# FrontPanel.net
KiCad netlist of a schematic drawn in EAGLE
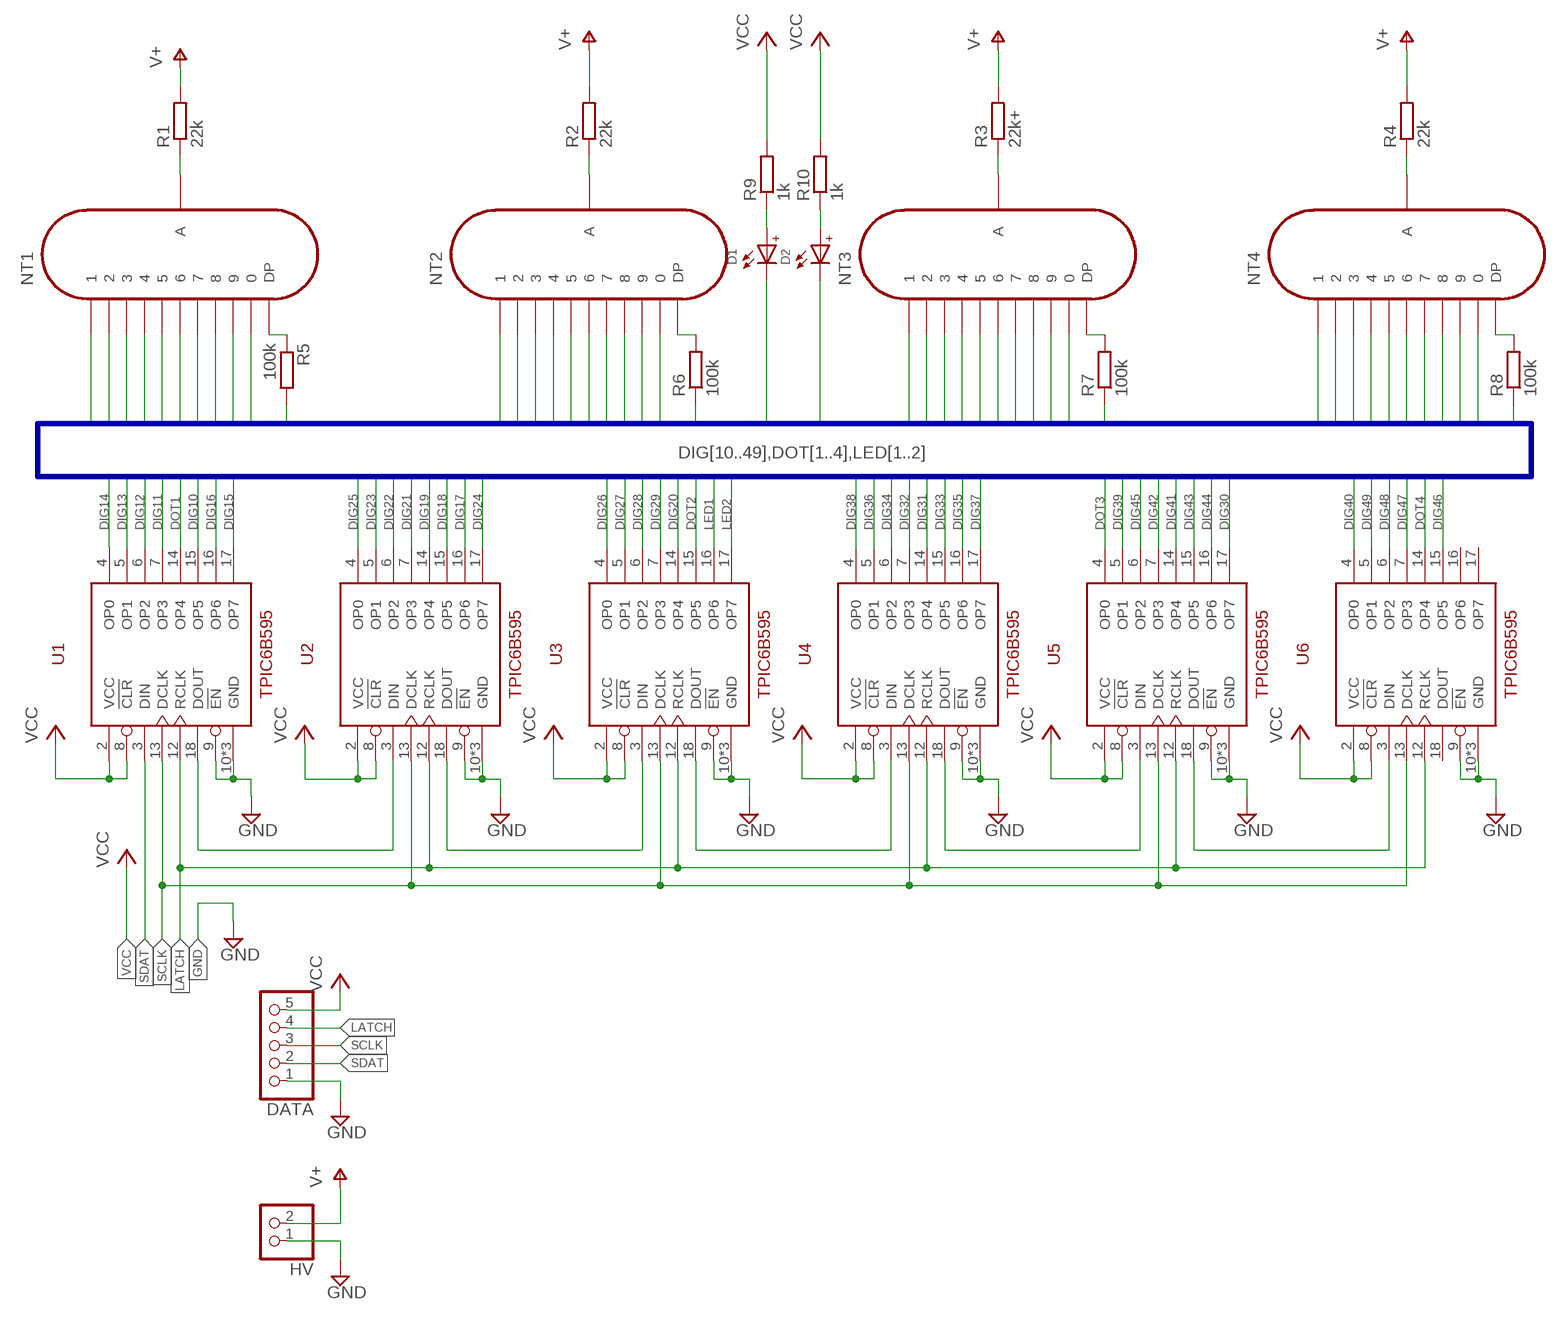
[diagram p0: schematic, sheet 1]

(export (version "E")
  (design (tool "Eeschema 10.0.6"))
  (components
    (comp (ref "D1")
      (value "RED/AMBER")
      (footprint "eagle-import:WL-SITW_154141XXBA210")
      (libsource (lib "eagle-import") (part "WL-SITW_3528_15414185BA210"))
    )
    (comp (ref "D2")
      (value "RED/AMBER")
      (footprint "eagle-import:WL-SITW_154141XXBA210")
      (libsource (lib "eagle-import") (part "WL-SITW_3528_15414185BA210"))
    )
    (comp (ref "DATA")
      (value ".1\" Header")
      (footprint "eagle-import:1X05")
      (libsource (lib "eagle-import") (part "PINHD-1X5"))
    )
    (comp (ref "HV")
      (value ".1\" Header")
      (footprint "eagle-import:1X02")
      (libsource (lib "eagle-import") (part "PINHD-1X2"))
    )
    (comp (ref "NT1")
      (value "IN-12B")
      (footprint "eagle-import:IN-12")
      (libsource (lib "eagle-import") (part "IN-12B"))
    )
    (comp (ref "NT2")
      (value "IN-12B")
      (footprint "eagle-import:IN-12")
      (libsource (lib "eagle-import") (part "IN-12B"))
    )
    (comp (ref "NT3")
      (value "IN-12B")
      (footprint "eagle-import:IN-12")
      (libsource (lib "eagle-import") (part "IN-12B"))
    )
    (comp (ref "NT4")
      (value "IN-12B")
      (footprint "eagle-import:IN-12")
      (libsource (lib "eagle-import") (part "IN-12B"))
    )
    (comp (ref "R1")
      (value "22k")
      (footprint "eagle-import:0207_10")
      (libsource (lib "eagle-import") (part "R-EU_0207/10"))
    )
    (comp (ref "R2")
      (value "22k")
      (footprint "eagle-import:0207_10")
      (libsource (lib "eagle-import") (part "R-EU_0207/10"))
    )
    (comp (ref "R3")
      (value "22k+")
      (footprint "eagle-import:0207_10")
      (libsource (lib "eagle-import") (part "R-EU_0207/10"))
    )
    (comp (ref "R4")
      (value "22k")
      (footprint "eagle-import:0207_10")
      (libsource (lib "eagle-import") (part "R-EU_0207/10"))
    )
    (comp (ref "R5")
      (value "100k")
      (footprint "eagle-import:0207_10")
      (libsource (lib "eagle-import") (part "R-EU_0207/10"))
    )
    (comp (ref "R6")
      (value "100k")
      (footprint "eagle-import:0207_10")
      (libsource (lib "eagle-import") (part "R-EU_0207/10"))
    )
    (comp (ref "R7")
      (value "100k")
      (footprint "eagle-import:0207_10")
      (libsource (lib "eagle-import") (part "R-EU_0207/10"))
    )
    (comp (ref "R8")
      (value "100k")
      (footprint "eagle-import:0207_10")
      (libsource (lib "eagle-import") (part "R-EU_0207/10"))
    )
    (comp (ref "R9")
      (value "1k")
      (footprint "eagle-import:0207_10")
      (libsource (lib "eagle-import") (part "R-EU_0207/10"))
    )
    (comp (ref "R10")
      (value "1k")
      (footprint "eagle-import:0207_10")
      (libsource (lib "eagle-import") (part "R-EU_0207/10"))
    )
    (comp (ref "U1")
      (value "TPIC6B595N")
      (footprint "eagle-import:PDIP-20")
      (libsource (lib "eagle-import") (part "TPIC6B595N"))
    )
    (comp (ref "U2")
      (value "TPIC6B595N")
      (footprint "eagle-import:PDIP-20")
      (libsource (lib "eagle-import") (part "TPIC6B595N"))
    )
    (comp (ref "U3")
      (value "TPIC6B595N")
      (footprint "eagle-import:PDIP-20")
      (libsource (lib "eagle-import") (part "TPIC6B595N"))
    )
    (comp (ref "U4")
      (value "TPIC6B595N")
      (footprint "eagle-import:PDIP-20")
      (libsource (lib "eagle-import") (part "TPIC6B595N"))
    )
    (comp (ref "U5")
      (value "TPIC6B595N")
      (footprint "eagle-import:PDIP-20")
      (libsource (lib "eagle-import") (part "TPIC6B595N"))
    )
    (comp (ref "U6")
      (value "TPIC6B595N")
      (footprint "eagle-import:PDIP-20")
      (libsource (lib "eagle-import") (part "TPIC6B595N"))
    )
  )
  (nets
    (net (code "1") (name "/DIG10") (class "Default")
      (node (ref "NT1") (pin "0") (pinfunction "0_0") (pintype "bidirectional"))
      (node (ref "U1") (pin "15") (pinfunction "OP5_15") (pintype "open_collector"))
    )
    (net (code "2") (name "/DIG11") (class "Default")
      (node (ref "NT1") (pin "1") (pinfunction "1_1") (pintype "bidirectional"))
      (node (ref "U1") (pin "7") (pinfunction "OP3_7") (pintype "open_collector"))
    )
    (net (code "3") (name "/DIG12") (class "Default")
      (node (ref "NT1") (pin "2") (pinfunction "2_2") (pintype "bidirectional"))
      (node (ref "U1") (pin "6") (pinfunction "OP2_6") (pintype "open_collector"))
    )
    (net (code "4") (name "/DIG13") (class "Default")
      (node (ref "NT1") (pin "3") (pinfunction "3_3") (pintype "bidirectional"))
      (node (ref "U1") (pin "5") (pinfunction "OP1_5") (pintype "open_collector"))
    )
    (net (code "5") (name "/DIG14") (class "Default")
      (node (ref "NT1") (pin "4") (pinfunction "4_4") (pintype "bidirectional"))
      (node (ref "U1") (pin "4") (pinfunction "OP0_4") (pintype "open_collector"))
    )
    (net (code "6") (name "/DIG15") (class "Default")
      (node (ref "NT1") (pin "5") (pinfunction "5_5") (pintype "bidirectional"))
      (node (ref "U1") (pin "17") (pinfunction "OP7_17") (pintype "open_collector"))
    )
    (net (code "7") (name "/DIG16") (class "Default")
      (node (ref "NT1") (pin "6") (pinfunction "6_6") (pintype "bidirectional"))
      (node (ref "U1") (pin "16") (pinfunction "OP6_16") (pintype "open_collector"))
    )
    (net (code "8") (name "/DIG17") (class "Default")
      (node (ref "NT1") (pin "7") (pinfunction "7_7") (pintype "bidirectional"))
      (node (ref "U2") (pin "16") (pinfunction "OP6_16") (pintype "open_collector"))
    )
    (net (code "9") (name "/DIG18") (class "Default")
      (node (ref "NT1") (pin "8") (pinfunction "8_8") (pintype "bidirectional"))
      (node (ref "U2") (pin "15") (pinfunction "OP5_15") (pintype "open_collector"))
    )
    (net (code "10") (name "/DIG19") (class "Default")
      (node (ref "NT1") (pin "9") (pinfunction "9_9") (pintype "bidirectional"))
      (node (ref "U2") (pin "14") (pinfunction "OP4_14") (pintype "open_collector"))
    )
    (net (code "11") (name "/DIG20") (class "Default")
      (node (ref "NT2") (pin "0") (pinfunction "0_0") (pintype "bidirectional"))
      (node (ref "U3") (pin "14") (pinfunction "OP4_14") (pintype "open_collector"))
    )
    (net (code "12") (name "/DIG21") (class "Default")
      (node (ref "NT2") (pin "1") (pinfunction "1_1") (pintype "bidirectional"))
      (node (ref "U2") (pin "7") (pinfunction "OP3_7") (pintype "open_collector"))
    )
    (net (code "13") (name "/DIG22") (class "Default")
      (node (ref "NT2") (pin "2") (pinfunction "2_2") (pintype "bidirectional"))
      (node (ref "U2") (pin "6") (pinfunction "OP2_6") (pintype "open_collector"))
    )
    (net (code "14") (name "/DIG23") (class "Default")
      (node (ref "NT2") (pin "3") (pinfunction "3_3") (pintype "bidirectional"))
      (node (ref "U2") (pin "5") (pinfunction "OP1_5") (pintype "open_collector"))
    )
    (net (code "15") (name "/DIG24") (class "Default")
      (node (ref "NT2") (pin "4") (pinfunction "4_4") (pintype "bidirectional"))
      (node (ref "U2") (pin "17") (pinfunction "OP7_17") (pintype "open_collector"))
    )
    (net (code "16") (name "/DIG25") (class "Default")
      (node (ref "NT2") (pin "5") (pinfunction "5_5") (pintype "bidirectional"))
      (node (ref "U2") (pin "4") (pinfunction "OP0_4") (pintype "open_collector"))
    )
    (net (code "17") (name "/DIG26") (class "Default")
      (node (ref "NT2") (pin "6") (pinfunction "6_6") (pintype "bidirectional"))
      (node (ref "U3") (pin "4") (pinfunction "OP0_4") (pintype "open_collector"))
    )
    (net (code "18") (name "/DIG27") (class "Default")
      (node (ref "NT2") (pin "7") (pinfunction "7_7") (pintype "bidirectional"))
      (node (ref "U3") (pin "5") (pinfunction "OP1_5") (pintype "open_collector"))
    )
    (net (code "19") (name "/DIG28") (class "Default")
      (node (ref "NT2") (pin "8") (pinfunction "8_8") (pintype "bidirectional"))
      (node (ref "U3") (pin "6") (pinfunction "OP2_6") (pintype "open_collector"))
    )
    (net (code "20") (name "/DIG29") (class "Default")
      (node (ref "NT2") (pin "9") (pinfunction "9_9") (pintype "bidirectional"))
      (node (ref "U3") (pin "7") (pinfunction "OP3_7") (pintype "open_collector"))
    )
    (net (code "21") (name "/DIG30") (class "Default")
      (node (ref "NT3") (pin "0") (pinfunction "0_0") (pintype "bidirectional"))
      (node (ref "U5") (pin "17") (pinfunction "OP7_17") (pintype "open_collector"))
    )
    (net (code "22") (name "/DIG31") (class "Default")
      (node (ref "NT3") (pin "1") (pinfunction "1_1") (pintype "bidirectional"))
      (node (ref "U4") (pin "14") (pinfunction "OP4_14") (pintype "open_collector"))
    )
    (net (code "23") (name "/DIG32") (class "Default")
      (node (ref "NT3") (pin "2") (pinfunction "2_2") (pintype "bidirectional"))
      (node (ref "U4") (pin "7") (pinfunction "OP3_7") (pintype "open_collector"))
    )
    (net (code "24") (name "/DIG33") (class "Default")
      (node (ref "NT3") (pin "3") (pinfunction "3_3") (pintype "bidirectional"))
      (node (ref "U4") (pin "15") (pinfunction "OP5_15") (pintype "open_collector"))
    )
    (net (code "25") (name "/DIG34") (class "Default")
      (node (ref "NT3") (pin "4") (pinfunction "4_4") (pintype "bidirectional"))
      (node (ref "U4") (pin "6") (pinfunction "OP2_6") (pintype "open_collector"))
    )
    (net (code "26") (name "/DIG35") (class "Default")
      (node (ref "NT3") (pin "5") (pinfunction "5_5") (pintype "bidirectional"))
      (node (ref "U4") (pin "16") (pinfunction "OP6_16") (pintype "open_collector"))
    )
    (net (code "27") (name "/DIG36") (class "Default")
      (node (ref "NT3") (pin "6") (pinfunction "6_6") (pintype "bidirectional"))
      (node (ref "U4") (pin "5") (pinfunction "OP1_5") (pintype "open_collector"))
    )
    (net (code "28") (name "/DIG37") (class "Default")
      (node (ref "NT3") (pin "7") (pinfunction "7_7") (pintype "bidirectional"))
      (node (ref "U4") (pin "17") (pinfunction "OP7_17") (pintype "open_collector"))
    )
    (net (code "29") (name "/DIG38") (class "Default")
      (node (ref "NT3") (pin "8") (pinfunction "8_8") (pintype "bidirectional"))
      (node (ref "U4") (pin "4") (pinfunction "OP0_4") (pintype "open_collector"))
    )
    (net (code "30") (name "/DIG39") (class "Default")
      (node (ref "NT3") (pin "9") (pinfunction "9_9") (pintype "bidirectional"))
      (node (ref "U5") (pin "5") (pinfunction "OP1_5") (pintype "open_collector"))
    )
    (net (code "31") (name "/DIG40") (class "Default")
      (node (ref "NT4") (pin "0") (pinfunction "0_0") (pintype "bidirectional"))
      (node (ref "U6") (pin "4") (pinfunction "OP0_4") (pintype "open_collector"))
    )
    (net (code "32") (name "/DIG41") (class "Default")
      (node (ref "NT4") (pin "1") (pinfunction "1_1") (pintype "bidirectional"))
      (node (ref "U5") (pin "14") (pinfunction "OP4_14") (pintype "open_collector"))
    )
    (net (code "33") (name "/DIG42") (class "Default")
      (node (ref "NT4") (pin "2") (pinfunction "2_2") (pintype "bidirectional"))
      (node (ref "U5") (pin "7") (pinfunction "OP3_7") (pintype "open_collector"))
    )
    (net (code "34") (name "/DIG43") (class "Default")
      (node (ref "NT4") (pin "3") (pinfunction "3_3") (pintype "bidirectional"))
      (node (ref "U5") (pin "15") (pinfunction "OP5_15") (pintype "open_collector"))
    )
    (net (code "35") (name "/DIG44") (class "Default")
      (node (ref "NT4") (pin "4") (pinfunction "4_4") (pintype "bidirectional"))
      (node (ref "U5") (pin "16") (pinfunction "OP6_16") (pintype "open_collector"))
    )
    (net (code "36") (name "/DIG45") (class "Default")
      (node (ref "NT4") (pin "5") (pinfunction "5_5") (pintype "bidirectional"))
      (node (ref "U5") (pin "6") (pinfunction "OP2_6") (pintype "open_collector"))
    )
    (net (code "37") (name "/DIG46") (class "Default")
      (node (ref "NT4") (pin "6") (pinfunction "6_6") (pintype "bidirectional"))
      (node (ref "U6") (pin "15") (pinfunction "OP5_15") (pintype "open_collector"))
    )
    (net (code "38") (name "/DIG47") (class "Default")
      (node (ref "NT4") (pin "7") (pinfunction "7_7") (pintype "bidirectional"))
      (node (ref "U6") (pin "7") (pinfunction "OP3_7") (pintype "open_collector"))
    )
    (net (code "39") (name "/DIG48") (class "Default")
      (node (ref "NT4") (pin "8") (pinfunction "8_8") (pintype "bidirectional"))
      (node (ref "U6") (pin "6") (pinfunction "OP2_6") (pintype "open_collector"))
    )
    (net (code "40") (name "/DIG49") (class "Default")
      (node (ref "NT4") (pin "9") (pinfunction "9_9") (pintype "bidirectional"))
      (node (ref "U6") (pin "5") (pinfunction "OP1_5") (pintype "open_collector"))
    )
    (net (code "41") (name "/DOT1") (class "Default")
      (node (ref "R5") (pin "2") (pinfunction "2_2") (pintype "passive"))
      (node (ref "U1") (pin "14") (pinfunction "OP4_14") (pintype "open_collector"))
    )
    (net (code "42") (name "/DOT2") (class "Default")
      (node (ref "R6") (pin "1") (pinfunction "1_1") (pintype "passive"))
      (node (ref "U3") (pin "15") (pinfunction "OP5_15") (pintype "open_collector"))
    )
    (net (code "43") (name "/DOT3") (class "Default")
      (node (ref "R7") (pin "1") (pinfunction "1_1") (pintype "passive"))
      (node (ref "U5") (pin "4") (pinfunction "OP0_4") (pintype "open_collector"))
    )
    (net (code "44") (name "/DOT4") (class "Default")
      (node (ref "R8") (pin "1") (pinfunction "1_1") (pintype "passive"))
      (node (ref "U6") (pin "14") (pinfunction "OP4_14") (pintype "open_collector"))
    )
    (net (code "45") (name "/LED1") (class "Default")
      (node (ref "D1") (pin "2") (pinfunction "-_2") (pintype "passive"))
      (node (ref "U3") (pin "16") (pinfunction "OP6_16") (pintype "open_collector"))
    )
    (net (code "46") (name "/LED2") (class "Default")
      (node (ref "D2") (pin "2") (pinfunction "-_2") (pintype "passive"))
      (node (ref "U3") (pin "17") (pinfunction "OP7_17") (pintype "open_collector"))
    )
    (net (code "48") (name "GND") (class "Default")
      (node (ref "DATA") (pin "1") (pinfunction "1_1") (pintype "passive"))
      (node (ref "HV") (pin "1") (pinfunction "1_1") (pintype "passive"))
      (node (ref "U1") (pin "10") (pinfunction "GND_10") (pintype "power_in"))
      (node (ref "U1") (pin "11") (pinfunction "GND_11") (pintype "power_in"))
      (node (ref "U1") (pin "19") (pinfunction "GND_19") (pintype "power_in"))
      (node (ref "U1") (pin "9") (pinfunction "~{EN}_9") (pintype "input"))
      (node (ref "U2") (pin "10") (pinfunction "GND_10") (pintype "power_in"))
      (node (ref "U2") (pin "11") (pinfunction "GND_11") (pintype "power_in"))
      (node (ref "U2") (pin "19") (pinfunction "GND_19") (pintype "power_in"))
      (node (ref "U2") (pin "9") (pinfunction "~{EN}_9") (pintype "input"))
      (node (ref "U3") (pin "10") (pinfunction "GND_10") (pintype "power_in"))
      (node (ref "U3") (pin "11") (pinfunction "GND_11") (pintype "power_in"))
      (node (ref "U3") (pin "19") (pinfunction "GND_19") (pintype "power_in"))
      (node (ref "U3") (pin "9") (pinfunction "~{EN}_9") (pintype "input"))
      (node (ref "U4") (pin "10") (pinfunction "GND_10") (pintype "power_in"))
      (node (ref "U4") (pin "11") (pinfunction "GND_11") (pintype "power_in"))
      (node (ref "U4") (pin "19") (pinfunction "GND_19") (pintype "power_in"))
      (node (ref "U4") (pin "9") (pinfunction "~{EN}_9") (pintype "input"))
      (node (ref "U5") (pin "10") (pinfunction "GND_10") (pintype "power_in"))
      (node (ref "U5") (pin "11") (pinfunction "GND_11") (pintype "power_in"))
      (node (ref "U5") (pin "19") (pinfunction "GND_19") (pintype "power_in"))
      (node (ref "U5") (pin "9") (pinfunction "~{EN}_9") (pintype "input"))
      (node (ref "U6") (pin "10") (pinfunction "GND_10") (pintype "power_in"))
      (node (ref "U6") (pin "11") (pinfunction "GND_11") (pintype "power_in"))
      (node (ref "U6") (pin "19") (pinfunction "GND_19") (pintype "power_in"))
      (node (ref "U6") (pin "9") (pinfunction "~{EN}_9") (pintype "input"))
    )
    (net (code "49") (name "LATCH") (class "Default")
      (node (ref "DATA") (pin "4") (pinfunction "4_4") (pintype "passive"))
      (node (ref "U1") (pin "12") (pinfunction "RCLK_12") (pintype "input"))
      (node (ref "U2") (pin "12") (pinfunction "RCLK_12") (pintype "input"))
      (node (ref "U3") (pin "12") (pinfunction "RCLK_12") (pintype "input"))
      (node (ref "U4") (pin "12") (pinfunction "RCLK_12") (pintype "input"))
      (node (ref "U5") (pin "12") (pinfunction "RCLK_12") (pintype "input"))
      (node (ref "U6") (pin "12") (pinfunction "RCLK_12") (pintype "input"))
    )
    (net (code "50") (name "Net-(D1-+)") (class "Default")
      (node (ref "D1") (pin "1") (pinfunction "+_1") (pintype "passive"))
      (node (ref "R9") (pin "1") (pinfunction "1_1") (pintype "passive"))
    )
    (net (code "51") (name "Net-(D2-+)") (class "Default")
      (node (ref "D2") (pin "1") (pinfunction "+_1") (pintype "passive"))
      (node (ref "R10") (pin "1") (pinfunction "1_1") (pintype "passive"))
    )
    (net (code "52") (name "Net-(NT1-DP)") (class "Default")
      (node (ref "NT1") (pin "LHDP") (pinfunction "DP_LHDP") (pintype "bidirectional"))
      (node (ref "R5") (pin "1") (pinfunction "1_1") (pintype "passive"))
    )
    (net (code "53") (name "Net-(NT1-PadA)") (class "Default")
      (node (ref "NT1") (pin "A") (pinfunction "A_A") (pintype "bidirectional"))
      (node (ref "R1") (pin "1") (pinfunction "1_1") (pintype "passive"))
    )
    (net (code "54") (name "Net-(NT2-DP)") (class "Default")
      (node (ref "NT2") (pin "LHDP") (pinfunction "DP_LHDP") (pintype "bidirectional"))
      (node (ref "R6") (pin "2") (pinfunction "2_2") (pintype "passive"))
    )
    (net (code "55") (name "Net-(NT2-PadA)") (class "Default")
      (node (ref "NT2") (pin "A") (pinfunction "A_A") (pintype "bidirectional"))
      (node (ref "R2") (pin "1") (pinfunction "1_1") (pintype "passive"))
    )
    (net (code "56") (name "Net-(NT3-DP)") (class "Default")
      (node (ref "NT3") (pin "LHDP") (pinfunction "DP_LHDP") (pintype "bidirectional"))
      (node (ref "R7") (pin "2") (pinfunction "2_2") (pintype "passive"))
    )
    (net (code "57") (name "Net-(NT3-PadA)") (class "Default")
      (node (ref "NT3") (pin "A") (pinfunction "A_A") (pintype "bidirectional"))
      (node (ref "R3") (pin "1") (pinfunction "1_1") (pintype "passive"))
    )
    (net (code "58") (name "Net-(NT4-DP)") (class "Default")
      (node (ref "NT4") (pin "LHDP") (pinfunction "DP_LHDP") (pintype "bidirectional"))
      (node (ref "R8") (pin "2") (pinfunction "2_2") (pintype "passive"))
    )
    (net (code "59") (name "Net-(NT4-PadA)") (class "Default")
      (node (ref "NT4") (pin "A") (pinfunction "A_A") (pintype "bidirectional"))
      (node (ref "R4") (pin "1") (pinfunction "1_1") (pintype "passive"))
    )
    (net (code "60") (name "Net-(U1-DOUT)") (class "Default")
      (node (ref "U1") (pin "18") (pinfunction "DOUT_18") (pintype "output"))
      (node (ref "U2") (pin "3") (pinfunction "DIN_3") (pintype "input"))
    )
    (net (code "61") (name "Net-(U2-DOUT)") (class "Default")
      (node (ref "U2") (pin "18") (pinfunction "DOUT_18") (pintype "output"))
      (node (ref "U3") (pin "3") (pinfunction "DIN_3") (pintype "input"))
    )
    (net (code "62") (name "Net-(U3-DOUT)") (class "Default")
      (node (ref "U3") (pin "18") (pinfunction "DOUT_18") (pintype "output"))
      (node (ref "U4") (pin "3") (pinfunction "DIN_3") (pintype "input"))
    )
    (net (code "63") (name "Net-(U4-DOUT)") (class "Default")
      (node (ref "U4") (pin "18") (pinfunction "DOUT_18") (pintype "output"))
      (node (ref "U5") (pin "3") (pinfunction "DIN_3") (pintype "input"))
    )
    (net (code "64") (name "Net-(U5-DOUT)") (class "Default")
      (node (ref "U5") (pin "18") (pinfunction "DOUT_18") (pintype "output"))
      (node (ref "U6") (pin "3") (pinfunction "DIN_3") (pintype "input"))
    )
    (net (code "65") (name "SCLK") (class "Default")
      (node (ref "DATA") (pin "3") (pinfunction "3_3") (pintype "passive"))
      (node (ref "U1") (pin "13") (pinfunction "DCLK_13") (pintype "input"))
      (node (ref "U2") (pin "13") (pinfunction "DCLK_13") (pintype "input"))
      (node (ref "U3") (pin "13") (pinfunction "DCLK_13") (pintype "input"))
      (node (ref "U4") (pin "13") (pinfunction "DCLK_13") (pintype "input"))
      (node (ref "U5") (pin "13") (pinfunction "DCLK_13") (pintype "input"))
      (node (ref "U6") (pin "13") (pinfunction "DCLK_13") (pintype "input"))
    )
    (net (code "66") (name "SDAT") (class "Default")
      (node (ref "DATA") (pin "2") (pinfunction "2_2") (pintype "passive"))
      (node (ref "U1") (pin "3") (pinfunction "DIN_3") (pintype "input"))
    )
    (net (code "67") (name "V+") (class "Default")
      (node (ref "HV") (pin "2") (pinfunction "2_2") (pintype "passive"))
      (node (ref "R1") (pin "2") (pinfunction "2_2") (pintype "passive"))
      (node (ref "R2") (pin "2") (pinfunction "2_2") (pintype "passive"))
      (node (ref "R3") (pin "2") (pinfunction "2_2") (pintype "passive"))
      (node (ref "R4") (pin "2") (pinfunction "2_2") (pintype "passive"))
    )
    (net (code "68") (name "VCC") (class "Default")
      (node (ref "DATA") (pin "5") (pinfunction "5_5") (pintype "passive"))
      (node (ref "R10") (pin "2") (pinfunction "2_2") (pintype "passive"))
      (node (ref "R9") (pin "2") (pinfunction "2_2") (pintype "passive"))
      (node (ref "U1") (pin "2") (pinfunction "VCC_2") (pintype "power_in"))
      (node (ref "U1") (pin "8") (pinfunction "~{CLR}_8") (pintype "input"))
      (node (ref "U2") (pin "2") (pinfunction "VCC_2") (pintype "power_in"))
      (node (ref "U2") (pin "8") (pinfunction "~{CLR}_8") (pintype "input"))
      (node (ref "U3") (pin "2") (pinfunction "VCC_2") (pintype "power_in"))
      (node (ref "U3") (pin "8") (pinfunction "~{CLR}_8") (pintype "input"))
      (node (ref "U4") (pin "2") (pinfunction "VCC_2") (pintype "power_in"))
      (node (ref "U4") (pin "8") (pinfunction "~{CLR}_8") (pintype "input"))
      (node (ref "U5") (pin "2") (pinfunction "VCC_2") (pintype "power_in"))
      (node (ref "U5") (pin "8") (pinfunction "~{CLR}_8") (pintype "input"))
      (node (ref "U6") (pin "2") (pinfunction "VCC_2") (pintype "power_in"))
      (node (ref "U6") (pin "8") (pinfunction "~{CLR}_8") (pintype "input"))
    )
    (net (code "69") (name "unconnected-(U6-DOUT-Pad18)") (class "Default")
      (node (ref "U6") (pin "18") (pinfunction "DOUT_18") (pintype "output"))
    )
    (net (code "70") (name "unconnected-(U6-OP6-Pad16)") (class "Default")
      (node (ref "U6") (pin "16") (pinfunction "OP6_16") (pintype "open_collector"))
    )
    (net (code "71") (name "unconnected-(U6-OP7-Pad17)") (class "Default")
      (node (ref "U6") (pin "17") (pinfunction "OP7_17") (pintype "open_collector"))
    )
  )
)
